# SCK_Ambient_v1_0.net
KiCad netlist of a schematic drawn in EAGLE
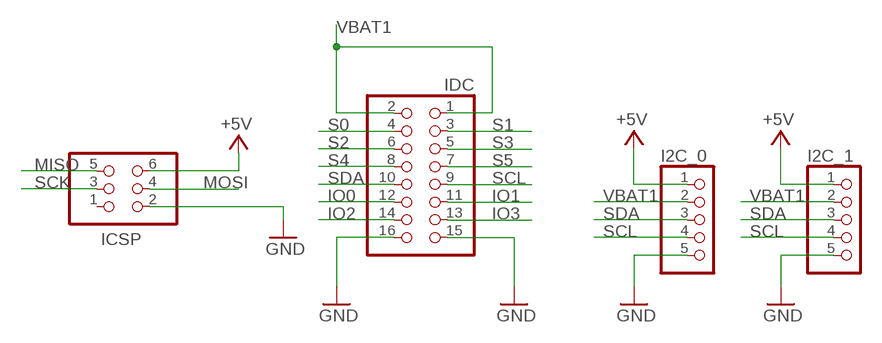
[diagram p0: schematic, sheet 1]
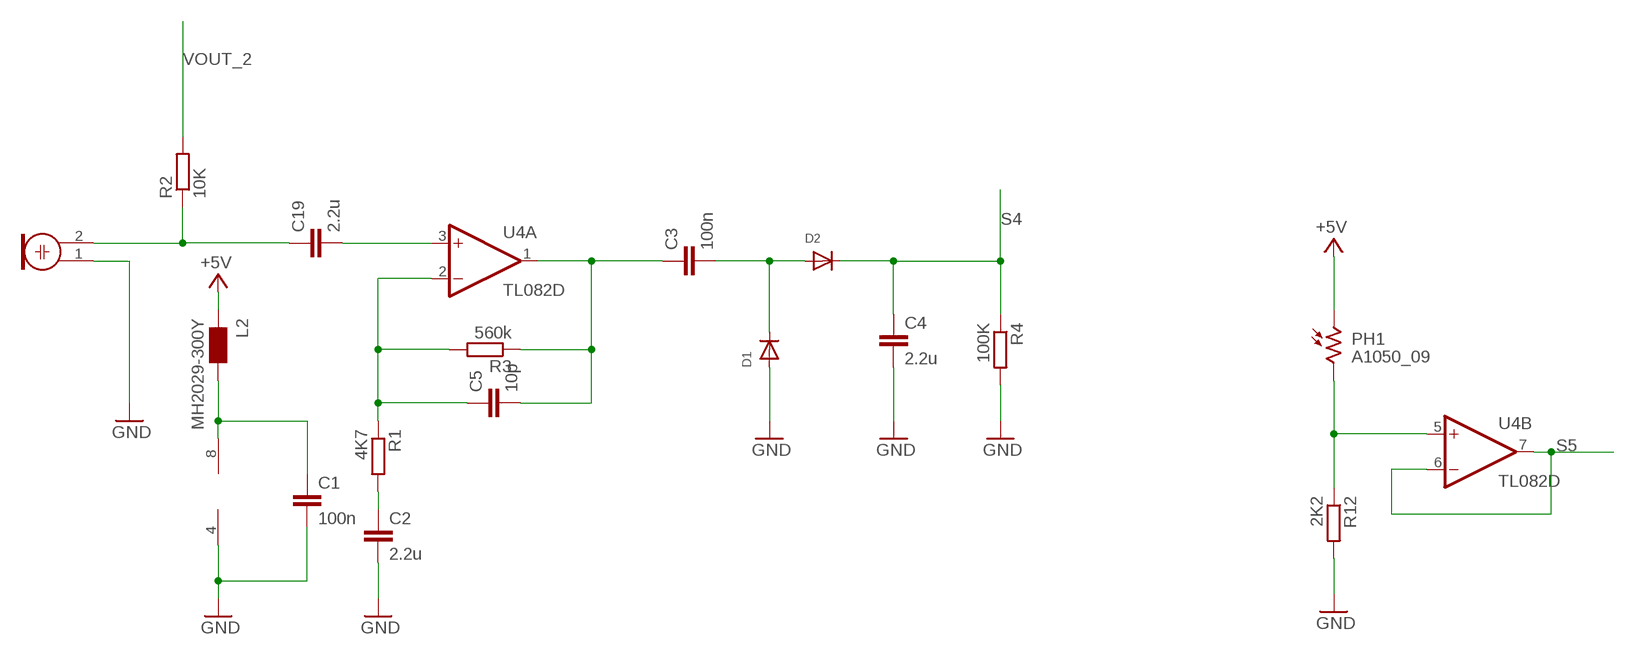
[diagram p1: schematic, sheet 2]
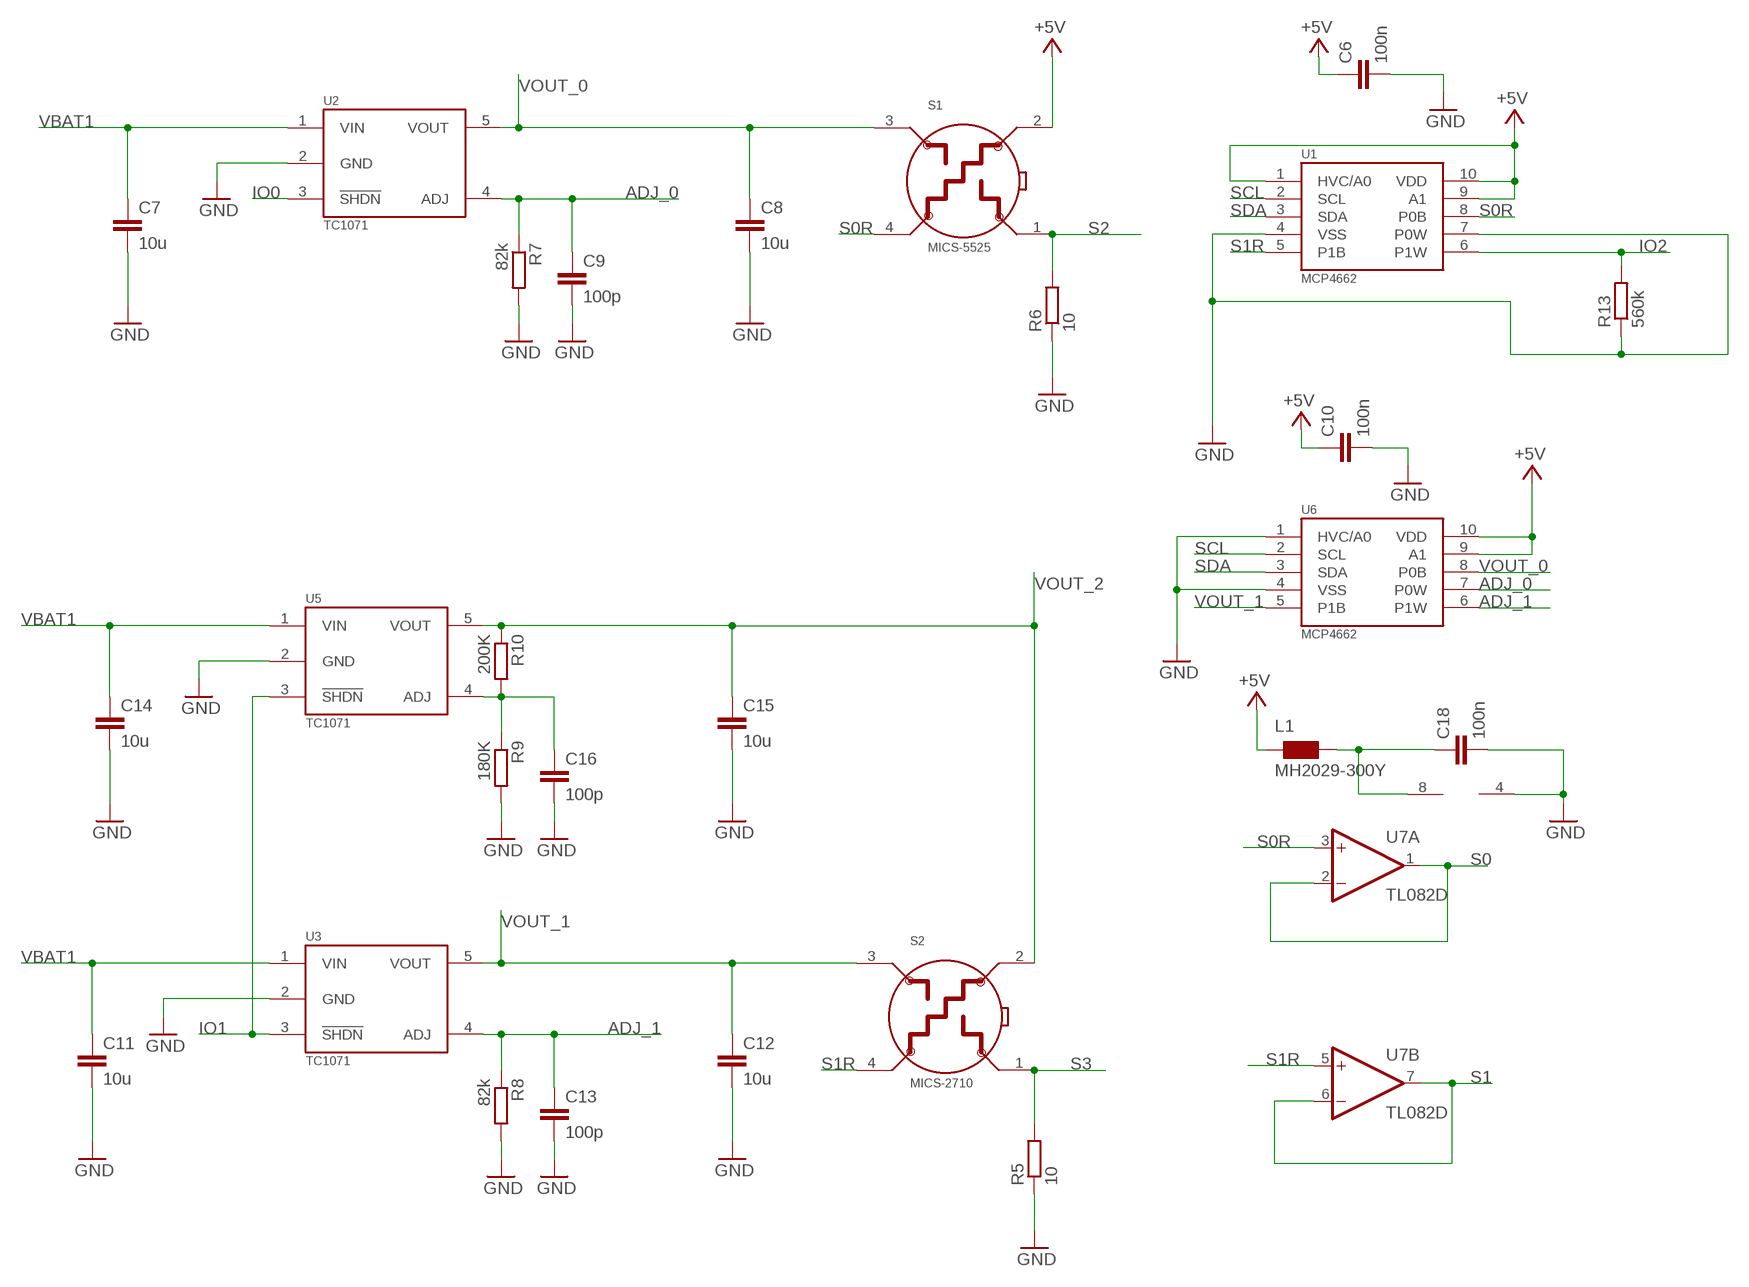
[diagram p2: schematic, sheet 3]
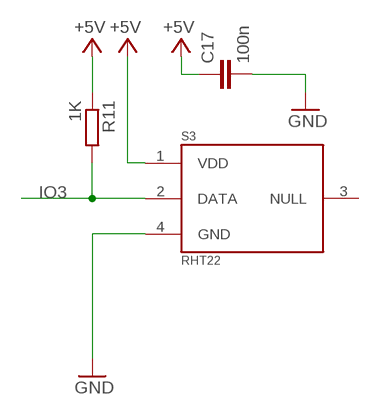
[diagram p3: schematic, sheet 4]

(export (version "E")
  (design (tool "Eeschema 10.0.6"))
  (components
    (comp (ref "C6")
      (value "100n")
      (footprint "eagle-import:C0805")
      (libsource (lib "eagle-import") (part "C-EUC0805"))
    )
    (comp (ref "C7")
      (value "10u")
      (footprint "eagle-import:C0805")
      (libsource (lib "eagle-import") (part "C-EUC0805"))
    )
    (comp (ref "C8")
      (value "10u")
      (footprint "eagle-import:C0805")
      (libsource (lib "eagle-import") (part "C-EUC0805"))
    )
    (comp (ref "C9")
      (value "100p")
      (footprint "eagle-import:C0805")
      (libsource (lib "eagle-import") (part "C-EUC0805"))
    )
    (comp (ref "C10")
      (value "100n")
      (footprint "eagle-import:C0805")
      (libsource (lib "eagle-import") (part "C-EUC0805"))
    )
    (comp (ref "C11")
      (value "10u")
      (footprint "eagle-import:C0805")
      (libsource (lib "eagle-import") (part "C-EUC0805"))
    )
    (comp (ref "C12")
      (value "10u")
      (footprint "eagle-import:C0805")
      (libsource (lib "eagle-import") (part "C-EUC0805"))
    )
    (comp (ref "C13")
      (value "100p")
      (footprint "eagle-import:C0805")
      (libsource (lib "eagle-import") (part "C-EUC0805"))
    )
    (comp (ref "C14")
      (value "10u")
      (footprint "eagle-import:C0805")
      (libsource (lib "eagle-import") (part "C-EUC0805"))
    )
    (comp (ref "C15")
      (value "10u")
      (footprint "eagle-import:C0805")
      (libsource (lib "eagle-import") (part "C-EUC0805"))
    )
    (comp (ref "C16")
      (value "100p")
      (footprint "eagle-import:C0805")
      (libsource (lib "eagle-import") (part "C-EUC0805"))
    )
    (comp (ref "C18")
      (value "100n")
      (footprint "eagle-import:C0805")
      (libsource (lib "eagle-import") (part "C-EUC0805"))
    )
    (comp (ref "L1")
      (value "MH2029-300Y")
      (footprint "eagle-import:0805")
      (libsource (lib "eagle-import") (part "WE-CBF_0805"))
    )
    (comp (ref "R5")
      (value "10")
      (footprint "eagle-import:R0805")
      (libsource (lib "eagle-import") (part "R-EU_R0805"))
    )
    (comp (ref "R6")
      (value "10")
      (footprint "eagle-import:R0805")
      (libsource (lib "eagle-import") (part "R-EU_R0805"))
    )
    (comp (ref "R7")
      (value "82k")
      (footprint "eagle-import:R0805")
      (libsource (lib "eagle-import") (part "R-EU_R0805"))
    )
    (comp (ref "R8")
      (value "82k")
      (footprint "eagle-import:R0805")
      (libsource (lib "eagle-import") (part "R-EU_R0805"))
    )
    (comp (ref "R9")
      (value "180K")
      (footprint "eagle-import:R0805")
      (libsource (lib "eagle-import") (part "R-EU_R0805"))
    )
    (comp (ref "R10")
      (value "200K")
      (footprint "eagle-import:R0805")
      (libsource (lib "eagle-import") (part "R-EU_R0805"))
    )
    (comp (ref "R13")
      (value "560k")
      (footprint "eagle-import:R0805")
      (libsource (lib "eagle-import") (part "R-EU_R0805"))
    )
    (comp (ref "S1")
      (value "MICS-5525")
      (footprint "eagle-import:E2V")
      (libsource (lib "eagle-import") (part "E2V{dblquote}"))
    )
    (comp (ref "S2")
      (value "MICS-2710")
      (footprint "eagle-import:E2V")
      (libsource (lib "eagle-import") (part "E2V{dblquote}"))
    )
    (comp (ref "U1")
      (value "MCP4662")
      (footprint "eagle-import:MSOP10")
      (libsource (lib "eagle-import") (part "MCP4662"))
    )
    (comp (ref "U2")
      (value "TC1071")
      (footprint "eagle-import:SOT23-5L")
      (libsource (lib "eagle-import") (part "TC1071"))
    )
    (comp (ref "U3")
      (value "TC1071")
      (footprint "eagle-import:SOT23-5L")
      (libsource (lib "eagle-import") (part "TC1071"))
    )
    (comp (ref "U5")
      (value "TC1071")
      (footprint "eagle-import:SOT23-5L")
      (libsource (lib "eagle-import") (part "TC1071"))
    )
    (comp (ref "U6")
      (value "MCP4662")
      (footprint "eagle-import:MSOP10")
      (libsource (lib "eagle-import") (part "MCP4662"))
    )
    (comp (ref "U7")
      (value "TL082D")
      (footprint "eagle-import:SO08")
      (libsource (lib "eagle-import") (part "TL082D"))
    )
    (comp (ref "C17")
      (value "100n")
      (footprint "eagle-import:C0805")
      (libsource (lib "eagle-import") (part "C-EUC0805"))
    )
    (comp (ref "R11")
      (value "1K")
      (footprint "eagle-import:R0805")
      (libsource (lib "eagle-import") (part "R-EU_R0805"))
    )
    (comp (ref "S3")
      (value "RHT22")
      (footprint "eagle-import:RHT22")
      (libsource (lib "eagle-import") (part "RHT22"))
    )
    (comp (ref "C1")
      (value "100n")
      (footprint "eagle-import:C0805")
      (libsource (lib "eagle-import") (part "C-EUC0805"))
    )
    (comp (ref "C2")
      (value "2.2u")
      (footprint "eagle-import:C0805")
      (libsource (lib "eagle-import") (part "C-EUC0805"))
    )
    (comp (ref "C3")
      (value "100n")
      (footprint "eagle-import:C0805")
      (libsource (lib "eagle-import") (part "C-EUC0805"))
    )
    (comp (ref "C4")
      (value "2.2u")
      (footprint "eagle-import:C0805")
      (libsource (lib "eagle-import") (part "C-EUC0805"))
    )
    (comp (ref "C5")
      (value "10p")
      (footprint "eagle-import:C0805")
      (libsource (lib "eagle-import") (part "C-EUC0805"))
    )
    (comp (ref "C19")
      (value "2.2u")
      (footprint "eagle-import:C0805")
      (libsource (lib "eagle-import") (part "C-EUC0805"))
    )
    (comp (ref "D1")
      (value "DIODESOD-123")
      (footprint "eagle-import:SOD-123")
      (libsource (lib "eagle-import") (part "DIODESOD-123"))
    )
    (comp (ref "D2")
      (value "DIODESOD-123")
      (footprint "eagle-import:SOD-123")
      (libsource (lib "eagle-import") (part "DIODESOD-123"))
    )
    (comp (ref "L2")
      (value "MH2029-300Y")
      (footprint "eagle-import:0805")
      (libsource (lib "eagle-import") (part "WE-CBF_0805"))
    )
    (comp (ref "M1")
      (value "ELECTRET_MICROPHON-WM-61A")
      (footprint "eagle-import:WM-61A")
      (libsource (lib "eagle-import") (part "ELECTRET_MICROPHON-WM-61A"))
    )
    (comp (ref "PH1")
      (value "A1050_09")
      (footprint "eagle-import:T0-46-A10XX")
      (libsource (lib "eagle-import") (part "A1050_09"))
    )
    (comp (ref "R1")
      (value "4K7")
      (footprint "eagle-import:R0805")
      (libsource (lib "eagle-import") (part "R-EU_R0805"))
    )
    (comp (ref "R2")
      (value "10K")
      (footprint "eagle-import:R0805")
      (libsource (lib "eagle-import") (part "R-EU_R0805"))
    )
    (comp (ref "R3")
      (value "560k")
      (footprint "eagle-import:R0805")
      (libsource (lib "eagle-import") (part "R-EU_R0805"))
    )
    (comp (ref "R4")
      (value "100K")
      (footprint "eagle-import:R0805")
      (libsource (lib "eagle-import") (part "R-EU_R0805"))
    )
    (comp (ref "R12")
      (value "2K2")
      (footprint "eagle-import:R0805")
      (libsource (lib "eagle-import") (part "R-EU_R0805"))
    )
    (comp (ref "U4")
      (value "TL082D")
      (footprint "eagle-import:SO08")
      (libsource (lib "eagle-import") (part "TL082D"))
    )
    (comp (ref "I2C_0")
      (value "PINHD-1X5")
      (footprint "eagle-import:1X05")
      (libsource (lib "eagle-import") (part "PINHD-1X5"))
    )
    (comp (ref "I2C_1")
      (value "PINHD-1X5")
      (footprint "eagle-import:1X05")
      (libsource (lib "eagle-import") (part "PINHD-1X5"))
    )
    (comp (ref "ICSP")
      (value "ICSP")
      (footprint "eagle-import:2X03")
      (libsource (lib "eagle-import") (part "PINHD-2X3"))
    )
    (comp (ref "IDC")
      (value "PINHD-2X8")
      (footprint "eagle-import:2X08")
      (libsource (lib "eagle-import") (part "PINHD-2X8"))
    )
  )
  (nets
    (net (code "1") (name "+5V") (class "Default")
      (node (ref "C10") (pin "1") (pinfunction "1_1") (pintype "passive"))
      (node (ref "C17") (pin "1") (pinfunction "1_1") (pintype "passive"))
      (node (ref "C6") (pin "1") (pinfunction "1_1") (pintype "passive"))
      (node (ref "I2C_0") (pin "1") (pinfunction "1_1") (pintype "passive"))
      (node (ref "I2C_1") (pin "1") (pinfunction "1_1") (pintype "passive"))
      (node (ref "ICSP") (pin "6") (pinfunction "6_6") (pintype "passive"))
      (node (ref "L1") (pin "1") (pinfunction "1_1") (pintype "passive"))
      (node (ref "L2") (pin "1") (pinfunction "1_1") (pintype "passive"))
      (node (ref "PH1") (pin "1") (pinfunction "1_1") (pintype "passive"))
      (node (ref "R11") (pin "1") (pinfunction "1_1") (pintype "passive"))
      (node (ref "S1") (pin "2") (pinfunction "2_2") (pintype "bidirectional"))
      (node (ref "S3") (pin "1") (pinfunction "VDD_1") (pintype "bidirectional"))
      (node (ref "U1") (pin "1") (pinfunction "HVC/A0_1") (pintype "bidirectional"))
      (node (ref "U1") (pin "10") (pinfunction "VDD_10") (pintype "bidirectional"))
      (node (ref "U1") (pin "9") (pinfunction "A1_9") (pintype "bidirectional"))
      (node (ref "U6") (pin "10") (pinfunction "VDD_10") (pintype "bidirectional"))
      (node (ref "U6") (pin "9") (pinfunction "A1_9") (pintype "bidirectional"))
    )
    (net (code "2") (name "ADJ_0") (class "Default")
      (node (ref "C9") (pin "1") (pinfunction "1_1") (pintype "passive"))
      (node (ref "R7") (pin "1") (pinfunction "1_1") (pintype "passive"))
      (node (ref "U2") (pin "4") (pinfunction "ADJ_4") (pintype "bidirectional"))
      (node (ref "U6") (pin "7") (pinfunction "P0W_7") (pintype "bidirectional"))
    )
    (net (code "3") (name "ADJ_1") (class "Default")
      (node (ref "C13") (pin "1") (pinfunction "1_1") (pintype "passive"))
      (node (ref "R8") (pin "1") (pinfunction "1_1") (pintype "passive"))
      (node (ref "U3") (pin "4") (pinfunction "ADJ_4") (pintype "bidirectional"))
      (node (ref "U6") (pin "6") (pinfunction "P1W_6") (pintype "bidirectional"))
    )
    (net (code "4") (name "GND") (class "Default")
      (node (ref "C1") (pin "2") (pinfunction "2_2") (pintype "passive"))
      (node (ref "C10") (pin "2") (pinfunction "2_2") (pintype "passive"))
      (node (ref "C11") (pin "2") (pinfunction "2_2") (pintype "passive"))
      (node (ref "C12") (pin "2") (pinfunction "2_2") (pintype "passive"))
      (node (ref "C13") (pin "2") (pinfunction "2_2") (pintype "passive"))
      (node (ref "C14") (pin "2") (pinfunction "2_2") (pintype "passive"))
      (node (ref "C15") (pin "2") (pinfunction "2_2") (pintype "passive"))
      (node (ref "C16") (pin "2") (pinfunction "2_2") (pintype "passive"))
      (node (ref "C17") (pin "2") (pinfunction "2_2") (pintype "passive"))
      (node (ref "C18") (pin "2") (pinfunction "2_2") (pintype "passive"))
      (node (ref "C2") (pin "2") (pinfunction "2_2") (pintype "passive"))
      (node (ref "C4") (pin "2") (pinfunction "2_2") (pintype "passive"))
      (node (ref "C6") (pin "2") (pinfunction "2_2") (pintype "passive"))
      (node (ref "C7") (pin "2") (pinfunction "2_2") (pintype "passive"))
      (node (ref "C8") (pin "2") (pinfunction "2_2") (pintype "passive"))
      (node (ref "C9") (pin "2") (pinfunction "2_2") (pintype "passive"))
      (node (ref "D1") (pin "A") (pinfunction "A_A") (pintype "passive"))
      (node (ref "I2C_0") (pin "5") (pinfunction "5_5") (pintype "passive"))
      (node (ref "I2C_1") (pin "5") (pinfunction "5_5") (pintype "passive"))
      (node (ref "ICSP") (pin "2") (pinfunction "2_2") (pintype "passive"))
      (node (ref "IDC") (pin "15") (pinfunction "15_15") (pintype "passive"))
      (node (ref "IDC") (pin "16") (pinfunction "16_16") (pintype "passive"))
      (node (ref "M1") (pin "1") (pinfunction "1_1") (pintype "passive"))
      (node (ref "R12") (pin "2") (pinfunction "2_2") (pintype "passive"))
      (node (ref "R13") (pin "1") (pinfunction "1_1") (pintype "passive"))
      (node (ref "R4") (pin "2") (pinfunction "2_2") (pintype "passive"))
      (node (ref "R5") (pin "1") (pinfunction "1_1") (pintype "passive"))
      (node (ref "R6") (pin "1") (pinfunction "1_1") (pintype "passive"))
      (node (ref "R7") (pin "2") (pinfunction "2_2") (pintype "passive"))
      (node (ref "R8") (pin "2") (pinfunction "2_2") (pintype "passive"))
      (node (ref "R9") (pin "2") (pinfunction "2_2") (pintype "passive"))
      (node (ref "S3") (pin "4") (pinfunction "GND_4") (pintype "bidirectional"))
      (node (ref "U1") (pin "4") (pinfunction "VSS_4") (pintype "bidirectional"))
      (node (ref "U1") (pin "7") (pinfunction "P0W_7") (pintype "bidirectional"))
      (node (ref "U2") (pin "2") (pinfunction "GND_2") (pintype "bidirectional"))
      (node (ref "U3") (pin "2") (pinfunction "GND_2") (pintype "bidirectional"))
      (node (ref "U4") (pin "4") (pinfunction "V-_4") (pintype "power_in"))
      (node (ref "U5") (pin "2") (pinfunction "GND_2") (pintype "bidirectional"))
      (node (ref "U6") (pin "1") (pinfunction "HVC/A0_1") (pintype "bidirectional"))
      (node (ref "U6") (pin "4") (pinfunction "VSS_4") (pintype "bidirectional"))
      (node (ref "U7") (pin "4") (pinfunction "V-_4") (pintype "power_in"))
    )
    (net (code "5") (name "IO0") (class "Default")
      (node (ref "IDC") (pin "12") (pinfunction "12_12") (pintype "passive"))
      (node (ref "U2") (pin "3") (pinfunction "~{SHDN}_3") (pintype "bidirectional"))
    )
    (net (code "6") (name "IO1") (class "Default")
      (node (ref "IDC") (pin "11") (pinfunction "11_11") (pintype "passive"))
      (node (ref "U3") (pin "3") (pinfunction "~{SHDN}_3") (pintype "bidirectional"))
      (node (ref "U5") (pin "3") (pinfunction "~{SHDN}_3") (pintype "bidirectional"))
    )
    (net (code "7") (name "IO2") (class "Default")
      (node (ref "IDC") (pin "14") (pinfunction "14_14") (pintype "passive"))
      (node (ref "R13") (pin "2") (pinfunction "2_2") (pintype "passive"))
      (node (ref "U1") (pin "6") (pinfunction "P1W_6") (pintype "bidirectional"))
    )
    (net (code "8") (name "IO3") (class "Default")
      (node (ref "IDC") (pin "13") (pinfunction "13_13") (pintype "passive"))
      (node (ref "R11") (pin "2") (pinfunction "2_2") (pintype "passive"))
      (node (ref "S3") (pin "2") (pinfunction "DATA_2") (pintype "bidirectional"))
    )
    (net (code "9") (name "MISO") (class "Default")
      (node (ref "ICSP") (pin "5") (pinfunction "5_5") (pintype "passive"))
    )
    (net (code "10") (name "MOSI") (class "Default")
      (node (ref "ICSP") (pin "4") (pinfunction "4_4") (pintype "passive"))
    )
    (net (code "11") (name "Net-(C2-Pad1)") (class "Default")
      (node (ref "C2") (pin "1") (pinfunction "1_1") (pintype "passive"))
      (node (ref "R1") (pin "2") (pinfunction "2_2") (pintype "passive"))
    )
    (net (code "12") (name "Net-(C3-Pad2)") (class "Default")
      (node (ref "C3") (pin "2") (pinfunction "2_2") (pintype "passive"))
      (node (ref "D1") (pin "C") (pinfunction "C_C") (pintype "passive"))
      (node (ref "D2") (pin "A") (pinfunction "A_A") (pintype "passive"))
    )
    (net (code "13") (name "Net-(C19-Pad1)") (class "Default")
      (node (ref "C19") (pin "1") (pinfunction "1_1") (pintype "passive"))
      (node (ref "M1") (pin "2") (pinfunction "2_2") (pintype "passive"))
      (node (ref "R2") (pin "1") (pinfunction "1_1") (pintype "passive"))
    )
    (net (code "14") (name "Net-(U4A-+IN)") (class "Default")
      (node (ref "C19") (pin "2") (pinfunction "2_2") (pintype "passive"))
      (node (ref "U4") (pin "3") (pinfunction "+IN_3") (pintype "input"))
    )
    (net (code "15") (name "Net-(U4A--IN)") (class "Default")
      (node (ref "C5") (pin "1") (pinfunction "1_1") (pintype "passive"))
      (node (ref "R1") (pin "1") (pinfunction "1_1") (pintype "passive"))
      (node (ref "R3") (pin "2") (pinfunction "2_2") (pintype "passive"))
      (node (ref "U4") (pin "2") (pinfunction "-IN_2") (pintype "input"))
    )
    (net (code "16") (name "Net-(U4A-OUT)") (class "Default")
      (node (ref "C3") (pin "1") (pinfunction "1_1") (pintype "passive"))
      (node (ref "C5") (pin "2") (pinfunction "2_2") (pintype "passive"))
      (node (ref "R3") (pin "1") (pinfunction "1_1") (pintype "passive"))
      (node (ref "U4") (pin "1") (pinfunction "OUT_1") (pintype "output"))
    )
    (net (code "17") (name "Net-(U4B-+IN)") (class "Default")
      (node (ref "PH1") (pin "2") (pinfunction "2_2") (pintype "passive"))
      (node (ref "R12") (pin "1") (pinfunction "1_1") (pintype "passive"))
      (node (ref "U4") (pin "5") (pinfunction "+IN_5") (pintype "input"))
    )
    (net (code "18") (name "Net-(U4C-V+)") (class "Default")
      (node (ref "C1") (pin "1") (pinfunction "1_1") (pintype "passive"))
      (node (ref "L2") (pin "2") (pinfunction "2_2") (pintype "passive"))
      (node (ref "U4") (pin "8") (pinfunction "V+_8") (pintype "power_in"))
    )
    (net (code "19") (name "Net-(U5-ADJ)") (class "Default")
      (node (ref "C16") (pin "1") (pinfunction "1_1") (pintype "passive"))
      (node (ref "R10") (pin "2") (pinfunction "2_2") (pintype "passive"))
      (node (ref "R9") (pin "1") (pinfunction "1_1") (pintype "passive"))
      (node (ref "U5") (pin "4") (pinfunction "ADJ_4") (pintype "bidirectional"))
    )
    (net (code "20") (name "Net-(U7C-V+)") (class "Default")
      (node (ref "C18") (pin "1") (pinfunction "1_1") (pintype "passive"))
      (node (ref "L1") (pin "2") (pinfunction "2_2") (pintype "passive"))
      (node (ref "U7") (pin "8") (pinfunction "V+_8") (pintype "power_in"))
    )
    (net (code "21") (name "S0") (class "Default")
      (node (ref "IDC") (pin "4") (pinfunction "4_4") (pintype "passive"))
      (node (ref "U7") (pin "1") (pinfunction "OUT_1") (pintype "output"))
      (node (ref "U7") (pin "2") (pinfunction "-IN_2") (pintype "input"))
    )
    (net (code "22") (name "S0R") (class "Default")
      (node (ref "S1") (pin "4") (pinfunction "4_4") (pintype "bidirectional"))
      (node (ref "U1") (pin "8") (pinfunction "P0B_8") (pintype "bidirectional"))
      (node (ref "U7") (pin "3") (pinfunction "+IN_3") (pintype "input"))
    )
    (net (code "23") (name "S1") (class "Default")
      (node (ref "IDC") (pin "3") (pinfunction "3_3") (pintype "passive"))
      (node (ref "U7") (pin "6") (pinfunction "-IN_6") (pintype "input"))
      (node (ref "U7") (pin "7") (pinfunction "OUT_7") (pintype "output"))
    )
    (net (code "24") (name "S1R") (class "Default")
      (node (ref "S2") (pin "4") (pinfunction "4_4") (pintype "bidirectional"))
      (node (ref "U1") (pin "5") (pinfunction "P1B_5") (pintype "bidirectional"))
      (node (ref "U7") (pin "5") (pinfunction "+IN_5") (pintype "input"))
    )
    (net (code "25") (name "S2") (class "Default")
      (node (ref "IDC") (pin "6") (pinfunction "6_6") (pintype "passive"))
      (node (ref "R6") (pin "2") (pinfunction "2_2") (pintype "passive"))
      (node (ref "S1") (pin "1") (pinfunction "1_1") (pintype "bidirectional"))
    )
    (net (code "26") (name "S3") (class "Default")
      (node (ref "IDC") (pin "5") (pinfunction "5_5") (pintype "passive"))
      (node (ref "R5") (pin "2") (pinfunction "2_2") (pintype "passive"))
      (node (ref "S2") (pin "1") (pinfunction "1_1") (pintype "bidirectional"))
    )
    (net (code "27") (name "S4") (class "Default")
      (node (ref "C4") (pin "1") (pinfunction "1_1") (pintype "passive"))
      (node (ref "D2") (pin "C") (pinfunction "C_C") (pintype "passive"))
      (node (ref "IDC") (pin "8") (pinfunction "8_8") (pintype "passive"))
      (node (ref "R4") (pin "1") (pinfunction "1_1") (pintype "passive"))
    )
    (net (code "28") (name "S5") (class "Default")
      (node (ref "IDC") (pin "7") (pinfunction "7_7") (pintype "passive"))
      (node (ref "U4") (pin "6") (pinfunction "-IN_6") (pintype "input"))
      (node (ref "U4") (pin "7") (pinfunction "OUT_7") (pintype "output"))
    )
    (net (code "29") (name "SCK") (class "Default")
      (node (ref "ICSP") (pin "3") (pinfunction "3_3") (pintype "passive"))
    )
    (net (code "30") (name "SCL") (class "Default")
      (node (ref "I2C_0") (pin "4") (pinfunction "4_4") (pintype "passive"))
      (node (ref "I2C_1") (pin "4") (pinfunction "4_4") (pintype "passive"))
      (node (ref "IDC") (pin "9") (pinfunction "9_9") (pintype "passive"))
      (node (ref "U1") (pin "2") (pinfunction "SCL_2") (pintype "bidirectional"))
      (node (ref "U6") (pin "2") (pinfunction "SCL_2") (pintype "bidirectional"))
    )
    (net (code "31") (name "SDA") (class "Default")
      (node (ref "I2C_0") (pin "3") (pinfunction "3_3") (pintype "passive"))
      (node (ref "I2C_1") (pin "3") (pinfunction "3_3") (pintype "passive"))
      (node (ref "IDC") (pin "10") (pinfunction "10_10") (pintype "passive"))
      (node (ref "U1") (pin "3") (pinfunction "SDA_3") (pintype "bidirectional"))
      (node (ref "U6") (pin "3") (pinfunction "SDA_3") (pintype "bidirectional"))
    )
    (net (code "32") (name "VBAT1") (class "Default")
      (node (ref "C11") (pin "1") (pinfunction "1_1") (pintype "passive"))
      (node (ref "C14") (pin "1") (pinfunction "1_1") (pintype "passive"))
      (node (ref "C7") (pin "1") (pinfunction "1_1") (pintype "passive"))
      (node (ref "I2C_0") (pin "2") (pinfunction "2_2") (pintype "passive"))
      (node (ref "I2C_1") (pin "2") (pinfunction "2_2") (pintype "passive"))
      (node (ref "IDC") (pin "1") (pinfunction "1_1") (pintype "passive"))
      (node (ref "IDC") (pin "2") (pinfunction "2_2") (pintype "passive"))
      (node (ref "U2") (pin "1") (pinfunction "VIN_1") (pintype "bidirectional"))
      (node (ref "U3") (pin "1") (pinfunction "VIN_1") (pintype "bidirectional"))
      (node (ref "U5") (pin "1") (pinfunction "VIN_1") (pintype "bidirectional"))
    )
    (net (code "33") (name "VOUT_0") (class "Default")
      (node (ref "C8") (pin "1") (pinfunction "1_1") (pintype "passive"))
      (node (ref "S1") (pin "3") (pinfunction "3_3") (pintype "bidirectional"))
      (node (ref "U2") (pin "5") (pinfunction "VOUT_5") (pintype "bidirectional"))
      (node (ref "U6") (pin "8") (pinfunction "P0B_8") (pintype "bidirectional"))
    )
    (net (code "34") (name "VOUT_1") (class "Default")
      (node (ref "C12") (pin "1") (pinfunction "1_1") (pintype "passive"))
      (node (ref "S2") (pin "3") (pinfunction "3_3") (pintype "bidirectional"))
      (node (ref "U3") (pin "5") (pinfunction "VOUT_5") (pintype "bidirectional"))
      (node (ref "U6") (pin "5") (pinfunction "P1B_5") (pintype "bidirectional"))
    )
    (net (code "35") (name "VOUT_2") (class "Default")
      (node (ref "C15") (pin "1") (pinfunction "1_1") (pintype "passive"))
      (node (ref "R10") (pin "1") (pinfunction "1_1") (pintype "passive"))
      (node (ref "R2") (pin "2") (pinfunction "2_2") (pintype "passive"))
      (node (ref "S2") (pin "2") (pinfunction "2_2") (pintype "bidirectional"))
      (node (ref "U5") (pin "5") (pinfunction "VOUT_5") (pintype "bidirectional"))
    )
    (net (code "36") (name "unconnected-(ICSP-Pad1)") (class "Default")
      (node (ref "ICSP") (pin "1") (pinfunction "1_1") (pintype "passive"))
    )
    (net (code "37") (name "unconnected-(S3-NULL-Pad3)") (class "Default")
      (node (ref "S3") (pin "3") (pinfunction "NULL_3") (pintype "bidirectional"))
    )
  )
)
